# ZX_Kempston.net
KiCad netlist of a schematic drawn in EAGLE
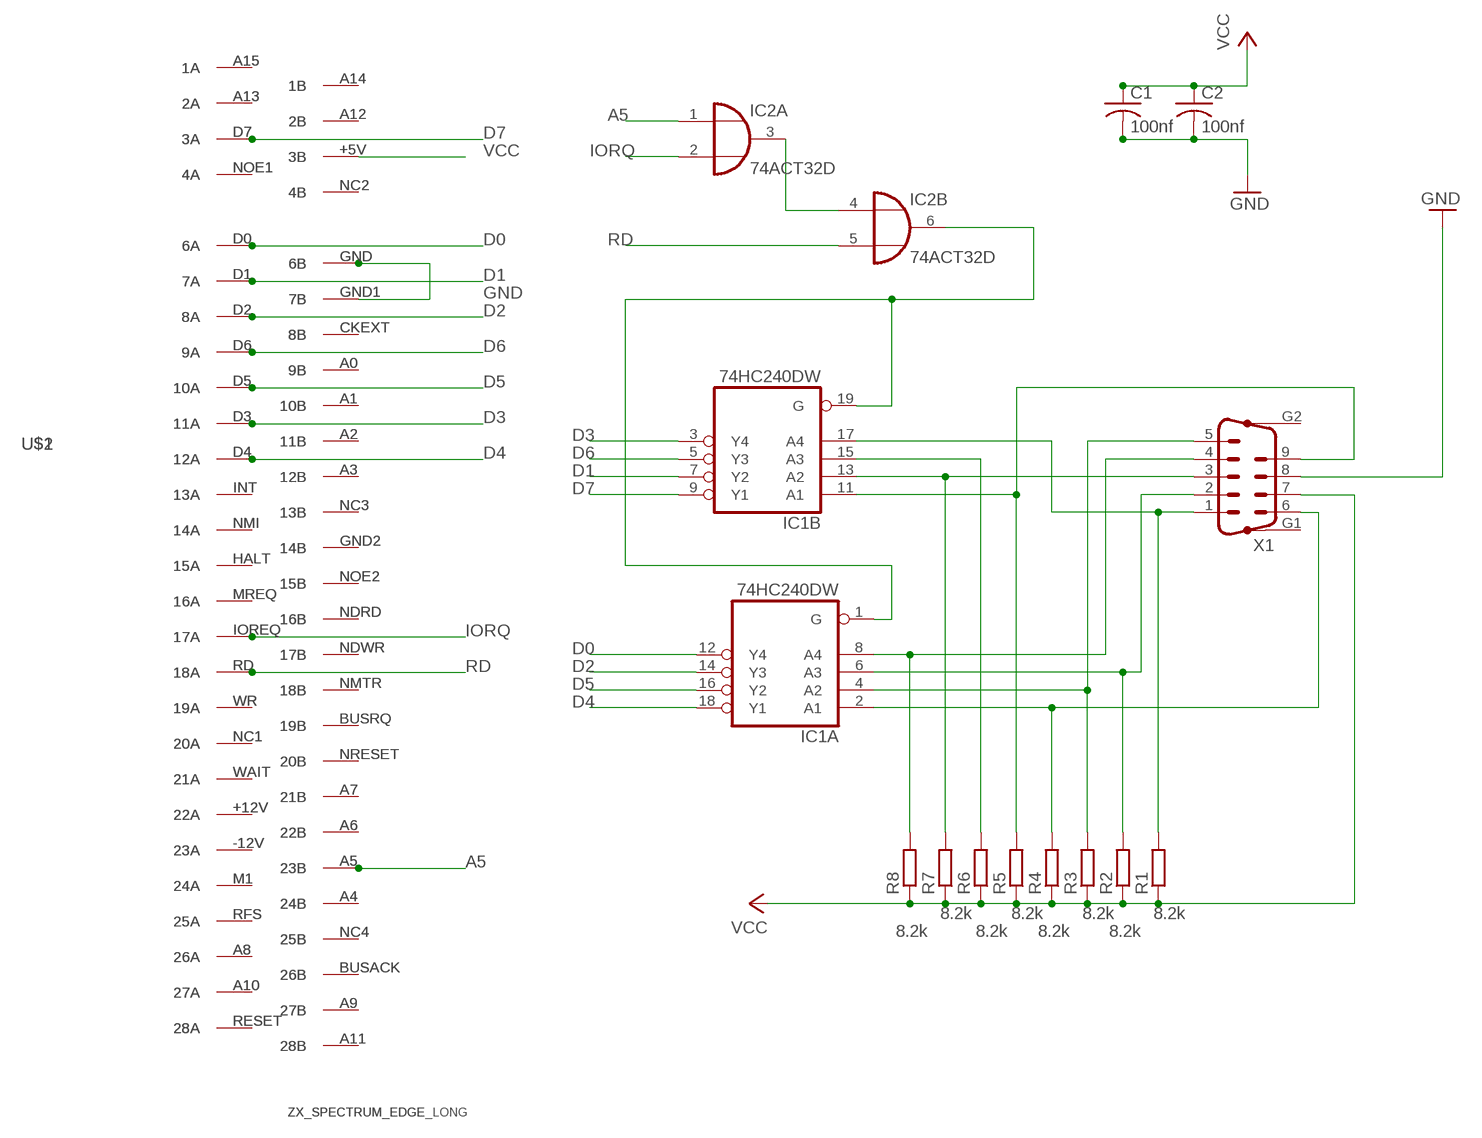
[diagram p0: schematic, sheet 1]

(export (version "E")
  (design (tool "Eeschema 10.0.6"))
  (components
    (comp (ref "C1")
      (value "100nf")
      (footprint "eagle-import:C0805")
      (libsource (lib "eagle-import") (part "C-USC0805"))
    )
    (comp (ref "C2")
      (value "100nf")
      (footprint "eagle-import:C0805")
      (libsource (lib "eagle-import") (part "C-USC0805"))
    )
    (comp (ref "IC1")
      (value "74HC240DW")
      (footprint "eagle-import:SO20W")
      (libsource (lib "eagle-import") (part "74240DWHC"))
    )
    (comp (ref "IC2")
      (value "74ACT32D")
      (footprint "eagle-import:SO14")
      (libsource (lib "eagle-import") (part "7432DACT"))
    )
    (comp (ref "R1")
      (value "8.2k")
      (footprint "eagle-import:M0805")
      (libsource (lib "eagle-import") (part "R-EU_M0805"))
    )
    (comp (ref "R2")
      (value "8.2k")
      (footprint "eagle-import:M0805")
      (libsource (lib "eagle-import") (part "R-EU_M0805"))
    )
    (comp (ref "R3")
      (value "8.2k")
      (footprint "eagle-import:M0805")
      (libsource (lib "eagle-import") (part "R-EU_M0805"))
    )
    (comp (ref "R4")
      (value "8.2k")
      (footprint "eagle-import:M0805")
      (libsource (lib "eagle-import") (part "R-EU_M0805"))
    )
    (comp (ref "R5")
      (value "8.2k")
      (footprint "eagle-import:M0805")
      (libsource (lib "eagle-import") (part "R-EU_M0805"))
    )
    (comp (ref "R6")
      (value "8.2k")
      (footprint "eagle-import:M0805")
      (libsource (lib "eagle-import") (part "R-EU_M0805"))
    )
    (comp (ref "R7")
      (value "8.2k")
      (footprint "eagle-import:M0805")
      (libsource (lib "eagle-import") (part "R-EU_M0805"))
    )
    (comp (ref "R8")
      (value "8.2k")
      (footprint "eagle-import:M0805")
      (libsource (lib "eagle-import") (part "R-EU_M0805"))
    )
    (comp (ref "U$1")
      (value "ZX_SPECTRUM_EDGE")
      (footprint "eagle-import:2X28_EDGE_2.54")
      (libsource (lib "eagle-import") (part "ZX_SPECTRUM_EDGE"))
    )
    (comp (ref "U$2")
      (value "ZX_SPECTRUM_EDGE_LONG")
      (footprint "eagle-import:2X28_EDGE_LONG")
      (libsource (lib "eagle-import") (part "ZX_SPECTRUM_EDGE_LONG"))
    )
    (comp (ref "X1")
      (value "M09VP")
      (footprint "eagle-import:M09VP")
      (libsource (lib "eagle-import") (part "M09VP"))
    )
  )
  (nets
    (net (code "1") (name "/A5") (class "Default")
      (node (ref "IC2") (pin "1") (pinfunction "I0_1") (pintype "input"))
      (node (ref "U$1") (pin "A5") (pinfunction "23B_A5") (pintype "bidirectional"))
      (node (ref "U$2") (pin "A5") (pinfunction "23B_A5") (pintype "bidirectional"))
    )
    (net (code "2") (name "/D0") (class "Default")
      (node (ref "IC1") (pin "12") (pinfunction "Y4_12") (pintype "tri_state"))
      (node (ref "U$1") (pin "D0") (pinfunction "6A_D0") (pintype "bidirectional"))
      (node (ref "U$2") (pin "D0") (pinfunction "6A_D0") (pintype "bidirectional"))
    )
    (net (code "3") (name "/D1") (class "Default")
      (node (ref "IC1") (pin "7") (pinfunction "Y2_7") (pintype "tri_state"))
      (node (ref "U$1") (pin "D1") (pinfunction "7A_D1") (pintype "bidirectional"))
      (node (ref "U$2") (pin "D1") (pinfunction "7A_D1") (pintype "bidirectional"))
    )
    (net (code "4") (name "/D2") (class "Default")
      (node (ref "IC1") (pin "14") (pinfunction "Y3_14") (pintype "tri_state"))
      (node (ref "U$1") (pin "D2") (pinfunction "8A_D2") (pintype "bidirectional"))
      (node (ref "U$2") (pin "D2") (pinfunction "8A_D2") (pintype "bidirectional"))
    )
    (net (code "5") (name "/D3") (class "Default")
      (node (ref "IC1") (pin "3") (pinfunction "Y4_3") (pintype "tri_state"))
      (node (ref "U$1") (pin "D3") (pinfunction "11A_D3") (pintype "bidirectional"))
      (node (ref "U$2") (pin "D3") (pinfunction "11A_D3") (pintype "bidirectional"))
    )
    (net (code "6") (name "/D4") (class "Default")
      (node (ref "IC1") (pin "18") (pinfunction "Y1_18") (pintype "tri_state"))
      (node (ref "U$1") (pin "D4") (pinfunction "12A_D4") (pintype "bidirectional"))
      (node (ref "U$2") (pin "D4") (pinfunction "12A_D4") (pintype "bidirectional"))
    )
    (net (code "7") (name "/D5") (class "Default")
      (node (ref "IC1") (pin "16") (pinfunction "Y2_16") (pintype "tri_state"))
      (node (ref "U$1") (pin "D5") (pinfunction "10A_D5") (pintype "bidirectional"))
      (node (ref "U$2") (pin "D5") (pinfunction "10A_D5") (pintype "bidirectional"))
    )
    (net (code "8") (name "/D6") (class "Default")
      (node (ref "IC1") (pin "5") (pinfunction "Y3_5") (pintype "tri_state"))
      (node (ref "U$1") (pin "D6") (pinfunction "9A_D6") (pintype "bidirectional"))
      (node (ref "U$2") (pin "D6") (pinfunction "9A_D6") (pintype "bidirectional"))
    )
    (net (code "9") (name "/D7") (class "Default")
      (node (ref "IC1") (pin "9") (pinfunction "Y1_9") (pintype "tri_state"))
      (node (ref "U$1") (pin "D7") (pinfunction "3A_D7") (pintype "bidirectional"))
      (node (ref "U$2") (pin "D7") (pinfunction "3A_D7") (pintype "bidirectional"))
    )
    (net (code "10") (name "/IORQ") (class "Default")
      (node (ref "IC2") (pin "2") (pinfunction "I1_2") (pintype "input"))
      (node (ref "U$1") (pin "IOREQ") (pinfunction "17A_IOREQ") (pintype "bidirectional"))
      (node (ref "U$2") (pin "IOREQ") (pinfunction "17A_IOREQ") (pintype "bidirectional"))
    )
    (net (code "11") (name "/RD") (class "Default")
      (node (ref "IC2") (pin "5") (pinfunction "I1_5") (pintype "input"))
      (node (ref "U$1") (pin "RD") (pinfunction "18A_RD") (pintype "bidirectional"))
      (node (ref "U$2") (pin "RD") (pinfunction "18A_RD") (pintype "bidirectional"))
    )
    (net (code "12") (name "GND") (class "Default")
      (node (ref "C1") (pin "2") (pinfunction "2_2") (pintype "passive"))
      (node (ref "C2") (pin "2") (pinfunction "2_2") (pintype "passive"))
      (node (ref "U$1") (pin "GND") (pinfunction "6B_GND") (pintype "bidirectional"))
      (node (ref "U$1") (pin "GND1") (pinfunction "7B_GND1") (pintype "bidirectional"))
      (node (ref "U$2") (pin "GND") (pinfunction "6B_GND") (pintype "bidirectional"))
      (node (ref "U$2") (pin "GND1") (pinfunction "7B_GND1") (pintype "bidirectional"))
      (node (ref "X1") (pin "8") (pinfunction "8_8") (pintype "passive"))
    )
    (net (code "13") (name "Net-(IC1A-A1)") (class "Default")
      (node (ref "IC1") (pin "2") (pinfunction "A1_2") (pintype "input"))
      (node (ref "R4") (pin "2") (pinfunction "2_2") (pintype "passive"))
      (node (ref "X1") (pin "6") (pinfunction "6_6") (pintype "passive"))
    )
    (net (code "14") (name "Net-(IC1A-A2)") (class "Default")
      (node (ref "IC1") (pin "4") (pinfunction "A2_4") (pintype "input"))
      (node (ref "R3") (pin "2") (pinfunction "2_2") (pintype "passive"))
      (node (ref "X1") (pin "5") (pinfunction "5_5") (pintype "passive"))
    )
    (net (code "15") (name "Net-(IC1A-A3)") (class "Default")
      (node (ref "IC1") (pin "6") (pinfunction "A3_6") (pintype "input"))
      (node (ref "R2") (pin "2") (pinfunction "2_2") (pintype "passive"))
      (node (ref "X1") (pin "2") (pinfunction "2_2") (pintype "passive"))
    )
    (net (code "16") (name "Net-(IC1A-A4)") (class "Default")
      (node (ref "IC1") (pin "8") (pinfunction "A4_8") (pintype "input"))
      (node (ref "R8") (pin "2") (pinfunction "2_2") (pintype "passive"))
      (node (ref "X1") (pin "4") (pinfunction "4_4") (pintype "passive"))
    )
    (net (code "17") (name "Net-(IC1A-G)") (class "Default")
      (node (ref "IC1") (pin "1") (pinfunction "G_1") (pintype "input"))
      (node (ref "IC1") (pin "19") (pinfunction "G_19") (pintype "input"))
      (node (ref "IC2") (pin "6") (pinfunction "O_6") (pintype "output"))
    )
    (net (code "18") (name "Net-(IC1B-A1)") (class "Default")
      (node (ref "IC1") (pin "11") (pinfunction "A1_11") (pintype "input"))
      (node (ref "R5") (pin "2") (pinfunction "2_2") (pintype "passive"))
      (node (ref "X1") (pin "9") (pinfunction "9_9") (pintype "passive"))
    )
    (net (code "19") (name "Net-(IC1B-A2)") (class "Default")
      (node (ref "IC1") (pin "13") (pinfunction "A2_13") (pintype "input"))
      (node (ref "R7") (pin "2") (pinfunction "2_2") (pintype "passive"))
      (node (ref "X1") (pin "3") (pinfunction "3_3") (pintype "passive"))
    )
    (net (code "20") (name "Net-(IC1B-A3)") (class "Default")
      (node (ref "IC1") (pin "15") (pinfunction "A3_15") (pintype "input"))
      (node (ref "R6") (pin "2") (pinfunction "2_2") (pintype "passive"))
    )
    (net (code "21") (name "Net-(IC1B-A4)") (class "Default")
      (node (ref "IC1") (pin "17") (pinfunction "A4_17") (pintype "input"))
      (node (ref "R1") (pin "2") (pinfunction "2_2") (pintype "passive"))
      (node (ref "X1") (pin "1") (pinfunction "1_1") (pintype "passive"))
    )
    (net (code "22") (name "Net-(IC2A-O)") (class "Default")
      (node (ref "IC2") (pin "3") (pinfunction "O_3") (pintype "output"))
      (node (ref "IC2") (pin "4") (pinfunction "I0_4") (pintype "input"))
    )
    (net (code "23") (name "Net-(U$1-1A)") (class "Default")
      (node (ref "U$1") (pin "A15") (pinfunction "1A_A15") (pintype "bidirectional"))
      (node (ref "U$2") (pin "A15") (pinfunction "1A_A15") (pintype "bidirectional"))
    )
    (net (code "24") (name "Net-(U$1-1B)") (class "Default")
      (node (ref "U$1") (pin "A14") (pinfunction "1B_A14") (pintype "bidirectional"))
      (node (ref "U$2") (pin "A14") (pinfunction "1B_A14") (pintype "bidirectional"))
    )
    (net (code "25") (name "Net-(U$1-2A)") (class "Default")
      (node (ref "U$1") (pin "A13") (pinfunction "2A_A13") (pintype "bidirectional"))
      (node (ref "U$2") (pin "A13") (pinfunction "2A_A13") (pintype "bidirectional"))
    )
    (net (code "26") (name "Net-(U$1-2B)") (class "Default")
      (node (ref "U$1") (pin "A12") (pinfunction "2B_A12") (pintype "bidirectional"))
      (node (ref "U$2") (pin "A12") (pinfunction "2B_A12") (pintype "bidirectional"))
    )
    (net (code "27") (name "Net-(U$1-4A)") (class "Default")
      (node (ref "U$1") (pin "NOE1") (pinfunction "4A_NOE1") (pintype "bidirectional"))
      (node (ref "U$2") (pin "NOE1") (pinfunction "4A_NOE1") (pintype "bidirectional"))
    )
    (net (code "28") (name "Net-(U$1-4B)") (class "Default")
      (node (ref "U$1") (pin "NC2") (pinfunction "4B_NC2") (pintype "bidirectional"))
      (node (ref "U$2") (pin "NC2") (pinfunction "4B_NC2") (pintype "bidirectional"))
    )
    (net (code "29") (name "Net-(U$1-8B)") (class "Default")
      (node (ref "U$1") (pin "CKEXT") (pinfunction "8B_CKEXT") (pintype "bidirectional"))
      (node (ref "U$2") (pin "CKEXT") (pinfunction "8B_CKEXT") (pintype "bidirectional"))
    )
    (net (code "30") (name "Net-(U$1-9B)") (class "Default")
      (node (ref "U$1") (pin "A0") (pinfunction "9B_A0") (pintype "bidirectional"))
      (node (ref "U$2") (pin "A0") (pinfunction "9B_A0") (pintype "bidirectional"))
    )
    (net (code "31") (name "Net-(U$1-10B)") (class "Default")
      (node (ref "U$1") (pin "A1") (pinfunction "10B_A1") (pintype "bidirectional"))
      (node (ref "U$2") (pin "A1") (pinfunction "10B_A1") (pintype "bidirectional"))
    )
    (net (code "32") (name "Net-(U$1-11B)") (class "Default")
      (node (ref "U$1") (pin "A2") (pinfunction "11B_A2") (pintype "bidirectional"))
      (node (ref "U$2") (pin "A2") (pinfunction "11B_A2") (pintype "bidirectional"))
    )
    (net (code "33") (name "Net-(U$1-12B)") (class "Default")
      (node (ref "U$1") (pin "A3") (pinfunction "12B_A3") (pintype "bidirectional"))
      (node (ref "U$2") (pin "A3") (pinfunction "12B_A3") (pintype "bidirectional"))
    )
    (net (code "34") (name "Net-(U$1-13A)") (class "Default")
      (node (ref "U$1") (pin "INT") (pinfunction "13A_INT") (pintype "bidirectional"))
      (node (ref "U$2") (pin "INT") (pinfunction "13A_INT") (pintype "bidirectional"))
    )
    (net (code "35") (name "Net-(U$1-13B)") (class "Default")
      (node (ref "U$1") (pin "NC3") (pinfunction "13B_NC3") (pintype "bidirectional"))
      (node (ref "U$2") (pin "NC3") (pinfunction "13B_NC3") (pintype "bidirectional"))
    )
    (net (code "36") (name "Net-(U$1-14A)") (class "Default")
      (node (ref "U$1") (pin "NMI") (pinfunction "14A_NMI") (pintype "bidirectional"))
      (node (ref "U$2") (pin "NMI") (pinfunction "14A_NMI") (pintype "bidirectional"))
    )
    (net (code "37") (name "Net-(U$1-14B)") (class "Default")
      (node (ref "U$1") (pin "GND2") (pinfunction "14B_GND2") (pintype "bidirectional"))
      (node (ref "U$2") (pin "GND2") (pinfunction "14B_GND2") (pintype "bidirectional"))
    )
    (net (code "38") (name "Net-(U$1-15A)") (class "Default")
      (node (ref "U$1") (pin "HALT") (pinfunction "15A_HALT") (pintype "bidirectional"))
      (node (ref "U$2") (pin "HALT") (pinfunction "15A_HALT") (pintype "bidirectional"))
    )
    (net (code "39") (name "Net-(U$1-15B)") (class "Default")
      (node (ref "U$1") (pin "NOE2") (pinfunction "15B_NOE2") (pintype "bidirectional"))
      (node (ref "U$2") (pin "NOE2") (pinfunction "15B_NOE2") (pintype "bidirectional"))
    )
    (net (code "40") (name "Net-(U$1-16A)") (class "Default")
      (node (ref "U$1") (pin "MREQ") (pinfunction "16A_MREQ") (pintype "bidirectional"))
      (node (ref "U$2") (pin "MREQ") (pinfunction "16A_MREQ") (pintype "bidirectional"))
    )
    (net (code "41") (name "Net-(U$1-16B)") (class "Default")
      (node (ref "U$1") (pin "NDRD") (pinfunction "16B_NDRD") (pintype "bidirectional"))
      (node (ref "U$2") (pin "NDRD") (pinfunction "16B_NDRD") (pintype "bidirectional"))
    )
    (net (code "42") (name "Net-(U$1-17B)") (class "Default")
      (node (ref "U$1") (pin "NDWR") (pinfunction "17B_NDWR") (pintype "bidirectional"))
      (node (ref "U$2") (pin "NDWR") (pinfunction "17B_NDWR") (pintype "bidirectional"))
    )
    (net (code "43") (name "Net-(U$1-18B)") (class "Default")
      (node (ref "U$1") (pin "NMTR") (pinfunction "18B_NMTR") (pintype "bidirectional"))
      (node (ref "U$2") (pin "NMTR") (pinfunction "18B_NMTR") (pintype "bidirectional"))
    )
    (net (code "44") (name "Net-(U$1-19A)") (class "Default")
      (node (ref "U$1") (pin "WR") (pinfunction "19A_WR") (pintype "bidirectional"))
      (node (ref "U$2") (pin "WR") (pinfunction "19A_WR") (pintype "bidirectional"))
    )
    (net (code "45") (name "Net-(U$1-19B)") (class "Default")
      (node (ref "U$1") (pin "BUSRQ") (pinfunction "19B_BUSRQ") (pintype "bidirectional"))
      (node (ref "U$2") (pin "BUSRQ") (pinfunction "19B_BUSRQ") (pintype "bidirectional"))
    )
    (net (code "46") (name "Net-(U$1-20A)") (class "Default")
      (node (ref "U$1") (pin "NC1") (pinfunction "20A_NC1") (pintype "bidirectional"))
      (node (ref "U$2") (pin "NC1") (pinfunction "20A_NC1") (pintype "bidirectional"))
    )
    (net (code "47") (name "Net-(U$1-20B)") (class "Default")
      (node (ref "U$1") (pin "NRESET") (pinfunction "20B_NRESET") (pintype "bidirectional"))
      (node (ref "U$2") (pin "NRESET") (pinfunction "20B_NRESET") (pintype "bidirectional"))
    )
    (net (code "48") (name "Net-(U$1-21A)") (class "Default")
      (node (ref "U$1") (pin "WAIT") (pinfunction "21A_WAIT") (pintype "bidirectional"))
      (node (ref "U$2") (pin "WAIT") (pinfunction "21A_WAIT") (pintype "bidirectional"))
    )
    (net (code "49") (name "Net-(U$1-21B)") (class "Default")
      (node (ref "U$1") (pin "A7") (pinfunction "21B_A7") (pintype "bidirectional"))
      (node (ref "U$2") (pin "A7") (pinfunction "21B_A7") (pintype "bidirectional"))
    )
    (net (code "50") (name "Net-(U$1-22A)") (class "Default")
      (node (ref "U$1") (pin "+12V") (pinfunction "22A_+12V") (pintype "bidirectional"))
      (node (ref "U$2") (pin "+12V") (pinfunction "22A_+12V") (pintype "bidirectional"))
    )
    (net (code "51") (name "Net-(U$1-22B)") (class "Default")
      (node (ref "U$1") (pin "A6") (pinfunction "22B_A6") (pintype "bidirectional"))
      (node (ref "U$2") (pin "A6") (pinfunction "22B_A6") (pintype "bidirectional"))
    )
    (net (code "52") (name "Net-(U$1-23A)") (class "Default")
      (node (ref "U$1") (pin "-12V") (pinfunction "23A_-12V") (pintype "bidirectional"))
      (node (ref "U$2") (pin "-12V") (pinfunction "23A_-12V") (pintype "bidirectional"))
    )
    (net (code "53") (name "Net-(U$1-24A)") (class "Default")
      (node (ref "U$1") (pin "M1") (pinfunction "24A_M1") (pintype "bidirectional"))
      (node (ref "U$2") (pin "M1") (pinfunction "24A_M1") (pintype "bidirectional"))
    )
    (net (code "54") (name "Net-(U$1-24B)") (class "Default")
      (node (ref "U$1") (pin "A4") (pinfunction "24B_A4") (pintype "bidirectional"))
      (node (ref "U$2") (pin "A4") (pinfunction "24B_A4") (pintype "bidirectional"))
    )
    (net (code "55") (name "Net-(U$1-25A)") (class "Default")
      (node (ref "U$1") (pin "RFS") (pinfunction "25A_RFS") (pintype "bidirectional"))
      (node (ref "U$2") (pin "RFS") (pinfunction "25A_RFS") (pintype "bidirectional"))
    )
    (net (code "56") (name "Net-(U$1-25B)") (class "Default")
      (node (ref "U$1") (pin "NC4") (pinfunction "25B_NC4") (pintype "bidirectional"))
      (node (ref "U$2") (pin "NC4") (pinfunction "25B_NC4") (pintype "bidirectional"))
    )
    (net (code "57") (name "Net-(U$1-26A)") (class "Default")
      (node (ref "U$1") (pin "A8") (pinfunction "26A_A8") (pintype "bidirectional"))
      (node (ref "U$2") (pin "A8") (pinfunction "26A_A8") (pintype "bidirectional"))
    )
    (net (code "58") (name "Net-(U$1-26B)") (class "Default")
      (node (ref "U$1") (pin "BUSACK") (pinfunction "26B_BUSACK") (pintype "bidirectional"))
      (node (ref "U$2") (pin "BUSACK") (pinfunction "26B_BUSACK") (pintype "bidirectional"))
    )
    (net (code "59") (name "Net-(U$1-27A)") (class "Default")
      (node (ref "U$1") (pin "A10") (pinfunction "27A_A10") (pintype "bidirectional"))
      (node (ref "U$2") (pin "A10") (pinfunction "27A_A10") (pintype "bidirectional"))
    )
    (net (code "60") (name "Net-(U$1-27B)") (class "Default")
      (node (ref "U$1") (pin "A9") (pinfunction "27B_A9") (pintype "bidirectional"))
      (node (ref "U$2") (pin "A9") (pinfunction "27B_A9") (pintype "bidirectional"))
    )
    (net (code "61") (name "Net-(U$1-28A)") (class "Default")
      (node (ref "U$1") (pin "RESET") (pinfunction "28A_RESET") (pintype "bidirectional"))
      (node (ref "U$2") (pin "RESET") (pinfunction "28A_RESET") (pintype "bidirectional"))
    )
    (net (code "62") (name "Net-(U$1-28B)") (class "Default")
      (node (ref "U$1") (pin "A11") (pinfunction "28B_A11") (pintype "bidirectional"))
      (node (ref "U$2") (pin "A11") (pinfunction "28B_A11") (pintype "bidirectional"))
    )
    (net (code "63") (name "VCC") (class "Default")
      (node (ref "C1") (pin "1") (pinfunction "1_1") (pintype "passive"))
      (node (ref "C2") (pin "1") (pinfunction "1_1") (pintype "passive"))
      (node (ref "R1") (pin "1") (pinfunction "1_1") (pintype "passive"))
      (node (ref "R2") (pin "1") (pinfunction "1_1") (pintype "passive"))
      (node (ref "R3") (pin "1") (pinfunction "1_1") (pintype "passive"))
      (node (ref "R4") (pin "1") (pinfunction "1_1") (pintype "passive"))
      (node (ref "R5") (pin "1") (pinfunction "1_1") (pintype "passive"))
      (node (ref "R6") (pin "1") (pinfunction "1_1") (pintype "passive"))
      (node (ref "R7") (pin "1") (pinfunction "1_1") (pintype "passive"))
      (node (ref "R8") (pin "1") (pinfunction "1_1") (pintype "passive"))
      (node (ref "U$1") (pin "+5V") (pinfunction "3B_+5V") (pintype "bidirectional"))
      (node (ref "U$2") (pin "+5V") (pinfunction "3B_+5V") (pintype "bidirectional"))
      (node (ref "X1") (pin "7") (pinfunction "7_7") (pintype "passive"))
    )
    (net (code "64") (name "unconnected-(X1-PadG1)") (class "Default")
      (node (ref "X1") (pin "G1") (pinfunction "G1_G1") (pintype "passive"))
    )
    (net (code "65") (name "unconnected-(X1-PadG2)") (class "Default")
      (node (ref "X1") (pin "G2") (pinfunction "G2_G2") (pintype "passive"))
    )
  )
)
